# XL6009_fixed.net
KiCad netlist of a schematic drawn in Altium Designer
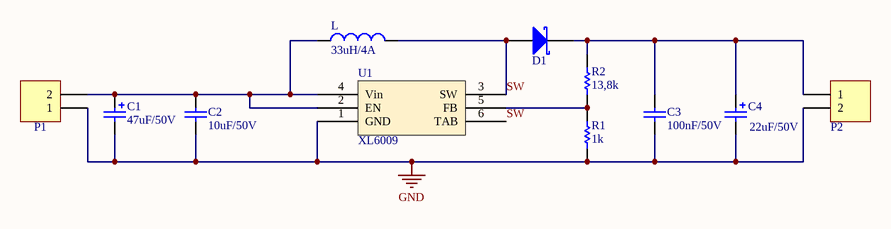
[diagram p0: XL6009 fixed.SchDoc]

(export (version "E")
  (design (tool "Eeschema 10.0.6"))
  (components
    (comp (ref "C1")
      (value "47uF/50V")
      (footprint "CAP ALU SIZE B")
      (description "Polarized Capacitor (Radial)")
      (fields (field (name "Comment") "Cap Pol SMD"))
      (libsource (lib "PIF_Library") (part "Cap Pol SMD"))
    )
    (comp (ref "C2")
      (value "10uF/50V")
      (footprint "CAP-SM-0805")
      (description "Capacitor")
      (fields (field (name "Comment") "Cap Non-Pol SMD"))
      (libsource (lib "PIF_Library") (part "Cap Non-Pol SMD"))
    )
    (comp (ref "C3")
      (value "100nF/50V")
      (footprint "CAP-SM-0805")
      (description "Capacitor")
      (fields (field (name "Comment") "Cap Non-Pol SMD"))
      (libsource (lib "PIF_Library") (part "Cap Non-Pol SMD"))
    )
    (comp (ref "C4")
      (value "22uF/50V")
      (footprint "CAP ALU SIZE B")
      (description "Polarized Capacitor (Radial)")
      (fields (field (name "Comment") "Cap Pol SMD"))
      (libsource (lib "PIF_Library") (part "Cap Pol SMD"))
    )
    (comp (ref "D1")
      (value "D Schottky")
      (footprint "SS34")
      (description "Schottky Diode")
      (fields (field (name "PUBLISHER") "Altium Limited"))
      (libsource (lib "PIF_Library") (part "D Schottky"))
    )
    (comp (ref "L")
      (value "33uH/4A")
      (footprint "INDUCTOR 12.5x12.5")
      (description "Inductor")
      (libsource (lib "PIF_Library") (part "Inductor"))
    )
    (comp (ref "P1")
      (value "Domino 2")
      (footprint "DOMINO 2- 5mm")
      (description "Domino, 2-Pin")
      (fields (field (name "PUBLISHER") "Altium Limited"))
      (libsource (lib "PIF_Library") (part "Domino 2"))
    )
    (comp (ref "P2")
      (value "Domino 2")
      (footprint "DOMINO 2- 5mm")
      (description "Domino, 2-Pin")
      (fields (field (name "PUBLISHER") "Altium Limited"))
      (libsource (lib "") (part "Domino 2_1"))
    )
    (comp (ref "R1")
      (value "1k")
      (footprint "RES-SM-0603")
      (description "Resistor")
      (fields (field (name "Comment") "RESISTOR SMD"))
      (libsource (lib "PIF_Library") (part "RESISTOR SMD"))
    )
    (comp (ref "R2")
      (value "13,8k")
      (footprint "RES-SM-0603")
      (description "Resistor")
      (fields (field (name "Comment") "RESISTOR SMD"))
      (libsource (lib "PIF_Library") (part "RESISTOR SMD"))
    )
    (comp (ref "U1")
      (value "XL6009")
      (footprint "LM2596")
      (description "SMD")
      (libsource (lib "buck&boost") (part "XL6009"))
    )
  )
  (nets
    (net (code "1") (name "/SW") (class "Default")
      (node (ref "D1") (pin "1") (pinfunction "A_1") (pintype "passive"))
      (node (ref "L") (pin "2") (pinfunction "2_2") (pintype "passive"))
      (node (ref "U1") (pin "3") (pinfunction "SW_3") (pintype "passive"))
      (node (ref "U1") (pin "6") (pinfunction "TAB_6") (pintype "passive"))
    )
    (net (code "2") (name "GND") (class "Default")
      (node (ref "C1") (pin "2") (pinfunction "2_2") (pintype "passive"))
      (node (ref "C2") (pin "1") (pinfunction "1_1") (pintype "passive"))
      (node (ref "C3") (pin "1") (pinfunction "1_1") (pintype "passive"))
      (node (ref "C4") (pin "2") (pinfunction "2_2") (pintype "passive"))
      (node (ref "P1") (pin "1") (pinfunction "1_1") (pintype "passive"))
      (node (ref "P2") (pin "2") (pinfunction "2_2") (pintype "passive"))
      (node (ref "R1") (pin "1") (pinfunction "1_1") (pintype "passive"))
      (node (ref "U1") (pin "1") (pinfunction "GND_1") (pintype "passive"))
    )
    (net (code "3") (name "Net-(D1-K)") (class "Default")
      (node (ref "C3") (pin "2") (pinfunction "2_2") (pintype "passive"))
      (node (ref "C4") (pin "1") (pinfunction "1_1") (pintype "passive"))
      (node (ref "D1") (pin "2") (pinfunction "K_2") (pintype "passive"))
      (node (ref "P2") (pin "1") (pinfunction "1_1") (pintype "passive"))
      (node (ref "R2") (pin "2") (pinfunction "2_2") (pintype "passive"))
    )
    (net (code "4") (name "Net-(U1-EN)") (class "Default")
      (node (ref "C1") (pin "1") (pinfunction "1_1") (pintype "passive"))
      (node (ref "C2") (pin "2") (pinfunction "2_2") (pintype "passive"))
      (node (ref "L") (pin "1") (pinfunction "1_1") (pintype "passive"))
      (node (ref "P1") (pin "2") (pinfunction "2_2") (pintype "passive"))
      (node (ref "U1") (pin "2") (pinfunction "EN_2") (pintype "passive"))
      (node (ref "U1") (pin "4") (pinfunction "Vin_4") (pintype "passive"))
    )
    (net (code "5") (name "Net-(U1-FB)") (class "Default")
      (node (ref "R1") (pin "2") (pinfunction "2_2") (pintype "passive"))
      (node (ref "R2") (pin "1") (pinfunction "1_1") (pintype "passive"))
      (node (ref "U1") (pin "5") (pinfunction "FB_5") (pintype "passive"))
    )
  )
)
